# SH7_-_LOAD_MONITORING_1.net
KiCad netlist of a schematic drawn in Altium Designer
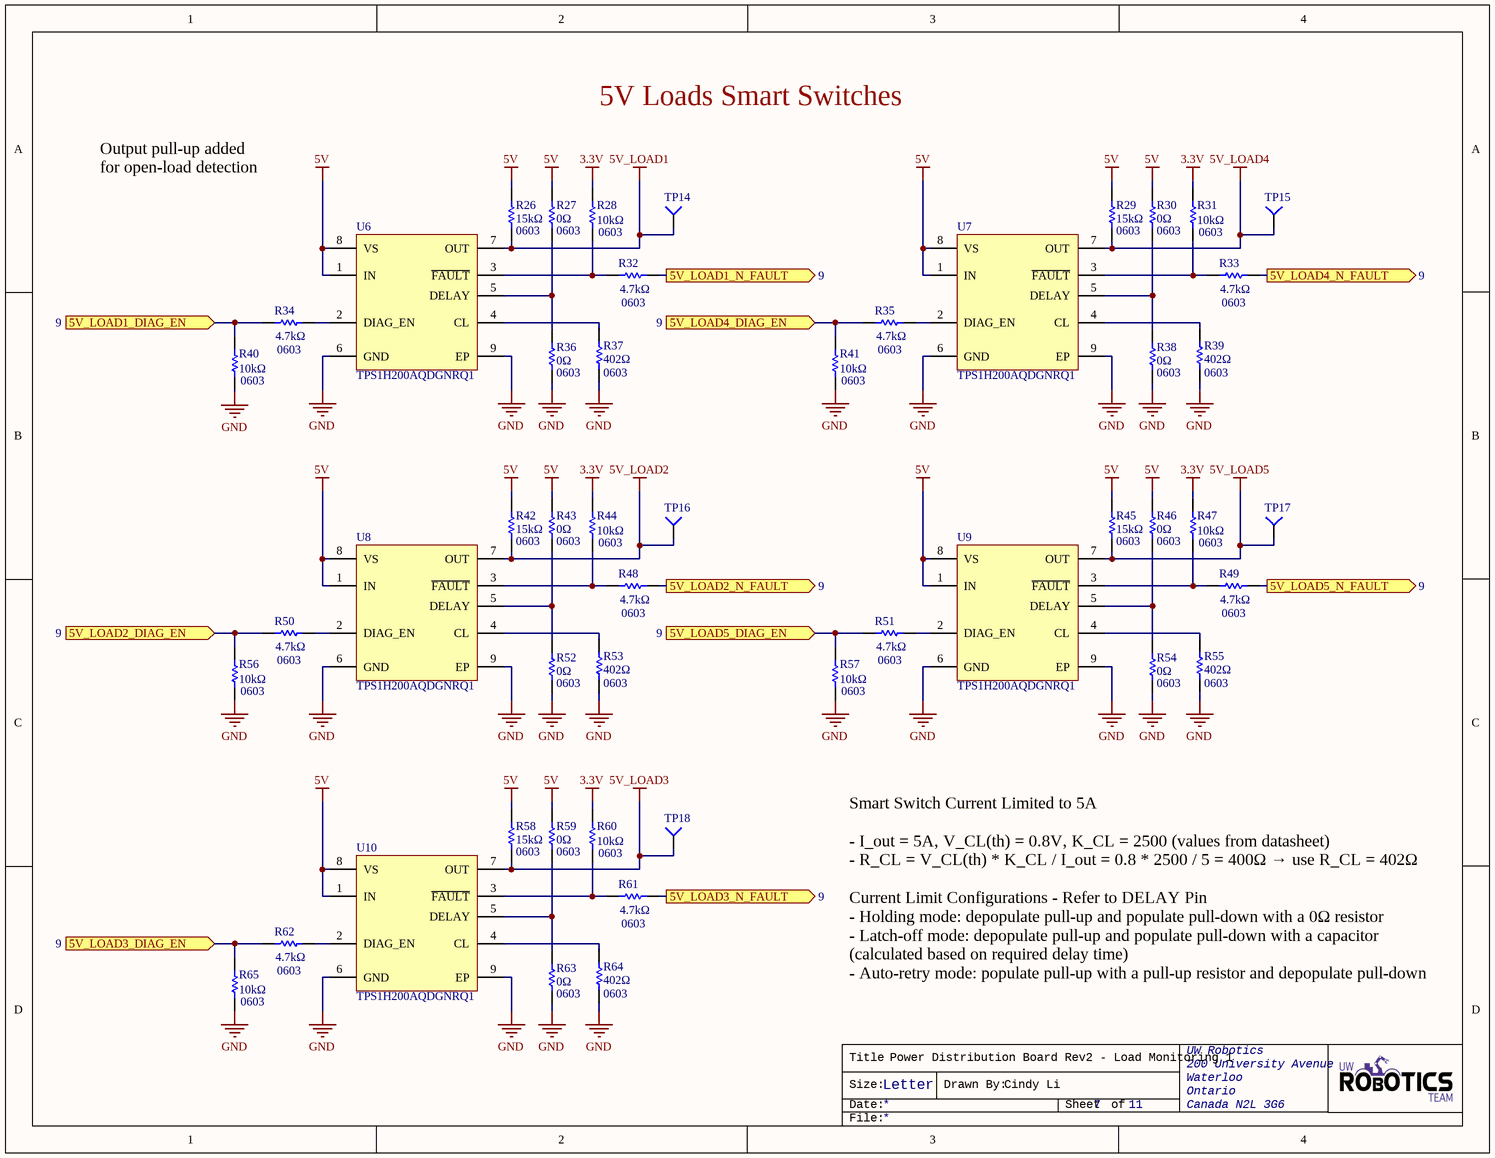
[diagram p0: SH7 - LOAD MONITORING 1.SchDoc]

(export (version "E")
  (design (tool "Eeschema 10.0.6"))
  (components
    (comp (ref "R26")
      (value "15kΩ")
      (footprint "RESC0603(1608)_N")
      (description "RES 15K OHM 5% 1/10W 0603")
      (fields
        (field (name "TOLERANCE") "5%")
        (field (name "CASE CODE (IMPERIAL)") "0603")
        (field (name "Comment") "RES_15kΩ_0603")
      )
      (libsource (lib "UWRT_Schematic_Library_2020") (part "RES_15kΩ_0603_5%"))
    )
    (comp (ref "R27")
      (value "0Ω")
      (footprint "RESC0603(1608)_N")
      (description "RES 0 OHM JUMPER 1/10W 0603")
      (fields (field (name "CASE CODE (IMPERIAL)") "0603") (field (name "Comment") "RES_0Ω_0603"))
      (libsource (lib "UWRT_Schematic_Library_2020") (part "RES_0Ω_0603"))
    )
    (comp (ref "R28")
      (value "10kΩ")
      (footprint "RESC0603(1608)_N")
      (description "RES 10K OHM 5% 1/10W 0603")
      (fields
        (field (name "TOLERANCE") "5%")
        (field (name "CASE CODE (IMPERIAL)") "0603")
        (field (name "Comment") "RES_10kΩ_0603")
      )
      (libsource (lib "UWRT_Schematic_Library_2020") (part "RES_10kΩ_0603_5%"))
    )
    (comp (ref "R29")
      (value "15kΩ")
      (footprint "RESC0603(1608)_N")
      (description "RES 15K OHM 5% 1/10W 0603")
      (fields
        (field (name "TOLERANCE") "5%")
        (field (name "CASE CODE (IMPERIAL)") "0603")
        (field (name "Comment") "RES_15kΩ_0603")
      )
      (libsource (lib "UWRT_Schematic_Library_2020") (part "RES_15kΩ_0603_5%"))
    )
    (comp (ref "R30")
      (value "0Ω")
      (footprint "RESC0603(1608)_N")
      (description "RES 0 OHM JUMPER 1/10W 0603")
      (fields (field (name "CASE CODE (IMPERIAL)") "0603") (field (name "Comment") "RES_0Ω_0603"))
      (libsource (lib "UWRT_Schematic_Library_2020") (part "RES_0Ω_0603"))
    )
    (comp (ref "R31")
      (value "10kΩ")
      (footprint "RESC0603(1608)_N")
      (description "RES 10K OHM 5% 1/10W 0603")
      (fields
        (field (name "TOLERANCE") "5%")
        (field (name "CASE CODE (IMPERIAL)") "0603")
        (field (name "Comment") "RES_10kΩ_0603")
      )
      (libsource (lib "UWRT_Schematic_Library_2020") (part "RES_10kΩ_0603_5%"))
    )
    (comp (ref "R32")
      (value "4.7kΩ")
      (footprint "RESC0603(1608)_N")
      (description "RES 4.7K OHM 5% 1/10W 0603")
      (fields
        (field (name "TOLERANCE") "5%")
        (field (name "CASE CODE (IMPERIAL)") "0603")
        (field (name "Comment") "RES_4.7kΩ_0603")
      )
      (libsource (lib "UWRT_Schematic_Library_2020") (part "RES_4.7kΩ_0603_5%"))
    )
    (comp (ref "R33")
      (value "4.7kΩ")
      (footprint "RESC0603(1608)_N")
      (description "RES 4.7K OHM 5% 1/10W 0603")
      (fields
        (field (name "TOLERANCE") "5%")
        (field (name "CASE CODE (IMPERIAL)") "0603")
        (field (name "Comment") "RES_4.7kΩ_0603")
      )
      (libsource (lib "UWRT_Schematic_Library_2020") (part "RES_4.7kΩ_0603_5%"))
    )
    (comp (ref "R34")
      (value "4.7kΩ")
      (footprint "RESC0603(1608)_N")
      (description "RES 4.7K OHM 5% 1/10W 0603")
      (fields
        (field (name "TOLERANCE") "5%")
        (field (name "CASE CODE (IMPERIAL)") "0603")
        (field (name "Comment") "RES_4.7kΩ_0603")
      )
      (libsource (lib "UWRT_Schematic_Library_2020") (part "RES_4.7kΩ_0603_5%"))
    )
    (comp (ref "R35")
      (value "4.7kΩ")
      (footprint "RESC0603(1608)_N")
      (description "RES 4.7K OHM 5% 1/10W 0603")
      (fields
        (field (name "TOLERANCE") "5%")
        (field (name "CASE CODE (IMPERIAL)") "0603")
        (field (name "Comment") "RES_4.7kΩ_0603")
      )
      (libsource (lib "UWRT_Schematic_Library_2020") (part "RES_4.7kΩ_0603_5%"))
    )
    (comp (ref "R36")
      (value "0Ω")
      (footprint "RESC0603(1608)_N")
      (description "RES 0 OHM JUMPER 1/10W 0603")
      (fields (field (name "CASE CODE (IMPERIAL)") "0603") (field (name "Comment") "RES_0Ω_0603"))
      (libsource (lib "UWRT_Schematic_Library_2020") (part "RES_0Ω_0603"))
    )
    (comp (ref "R37")
      (value "RES_402Ω_0603")
      (footprint "RESC0603(1608)_N")
      (description "RES SMD 402 OHM 0.5% 1/10W 0603")
      (fields
        (field (name "TOLERANCE") "0.5%")
        (field (name "RESISTANCE") "402Ω")
        (field (name "CASE CODE (IMPERIAL)") "0603")
      )
      (libsource (lib "UWRT_Schematic_Library_2020") (part "RES_402Ω_0603"))
    )
    (comp (ref "R38")
      (value "0Ω")
      (footprint "RESC0603(1608)_N")
      (description "RES 0 OHM JUMPER 1/10W 0603")
      (fields (field (name "CASE CODE (IMPERIAL)") "0603") (field (name "Comment") "RES_0Ω_0603"))
      (libsource (lib "UWRT_Schematic_Library_2020") (part "RES_0Ω_0603"))
    )
    (comp (ref "R39")
      (value "RES_402Ω_0603")
      (footprint "RESC0603(1608)_N")
      (description "RES SMD 402 OHM 0.5% 1/10W 0603")
      (fields
        (field (name "TOLERANCE") "0.5%")
        (field (name "RESISTANCE") "402Ω")
        (field (name "CASE CODE (IMPERIAL)") "0603")
      )
      (libsource (lib "UWRT_Schematic_Library_2020") (part "RES_402Ω_0603"))
    )
    (comp (ref "R40")
      (value "10kΩ")
      (footprint "RESC0603(1608)_N")
      (description "RES 10K OHM 5% 1/10W 0603")
      (fields
        (field (name "TOLERANCE") "5%")
        (field (name "CASE CODE (IMPERIAL)") "0603")
        (field (name "Comment") "RES_10kΩ_0603")
      )
      (libsource (lib "UWRT_Schematic_Library_2020") (part "RES_10kΩ_0603_5%"))
    )
    (comp (ref "R41")
      (value "10kΩ")
      (footprint "RESC0603(1608)_N")
      (description "RES 10K OHM 5% 1/10W 0603")
      (fields
        (field (name "TOLERANCE") "5%")
        (field (name "CASE CODE (IMPERIAL)") "0603")
        (field (name "Comment") "RES_10kΩ_0603")
      )
      (libsource (lib "UWRT_Schematic_Library_2020") (part "RES_10kΩ_0603_5%"))
    )
    (comp (ref "R42")
      (value "15kΩ")
      (footprint "RESC0603(1608)_N")
      (description "RES 15K OHM 5% 1/10W 0603")
      (fields
        (field (name "TOLERANCE") "5%")
        (field (name "CASE CODE (IMPERIAL)") "0603")
        (field (name "Comment") "RES_15kΩ_0603")
      )
      (libsource (lib "UWRT_Schematic_Library_2020") (part "RES_15kΩ_0603_5%"))
    )
    (comp (ref "R43")
      (value "0Ω")
      (footprint "RESC0603(1608)_N")
      (description "RES 0 OHM JUMPER 1/10W 0603")
      (fields (field (name "CASE CODE (IMPERIAL)") "0603") (field (name "Comment") "RES_0Ω_0603"))
      (libsource (lib "UWRT_Schematic_Library_2020") (part "RES_0Ω_0603"))
    )
    (comp (ref "R44")
      (value "10kΩ")
      (footprint "RESC0603(1608)_N")
      (description "RES 10K OHM 5% 1/10W 0603")
      (fields
        (field (name "TOLERANCE") "5%")
        (field (name "CASE CODE (IMPERIAL)") "0603")
        (field (name "Comment") "RES_10kΩ_0603")
      )
      (libsource (lib "UWRT_Schematic_Library_2020") (part "RES_10kΩ_0603_5%"))
    )
    (comp (ref "R45")
      (value "15kΩ")
      (footprint "RESC0603(1608)_N")
      (description "RES 15K OHM 5% 1/10W 0603")
      (fields
        (field (name "TOLERANCE") "5%")
        (field (name "CASE CODE (IMPERIAL)") "0603")
        (field (name "Comment") "RES_15kΩ_0603")
      )
      (libsource (lib "UWRT_Schematic_Library_2020") (part "RES_15kΩ_0603_5%"))
    )
    (comp (ref "R46")
      (value "0Ω")
      (footprint "RESC0603(1608)_N")
      (description "RES 0 OHM JUMPER 1/10W 0603")
      (fields (field (name "CASE CODE (IMPERIAL)") "0603") (field (name "Comment") "RES_0Ω_0603"))
      (libsource (lib "UWRT_Schematic_Library_2020") (part "RES_0Ω_0603"))
    )
    (comp (ref "R47")
      (value "10kΩ")
      (footprint "RESC0603(1608)_N")
      (description "RES 10K OHM 5% 1/10W 0603")
      (fields
        (field (name "TOLERANCE") "5%")
        (field (name "CASE CODE (IMPERIAL)") "0603")
        (field (name "Comment") "RES_10kΩ_0603")
      )
      (libsource (lib "UWRT_Schematic_Library_2020") (part "RES_10kΩ_0603_5%"))
    )
    (comp (ref "R48")
      (value "4.7kΩ")
      (footprint "RESC0603(1608)_N")
      (description "RES 4.7K OHM 5% 1/10W 0603")
      (fields
        (field (name "TOLERANCE") "5%")
        (field (name "CASE CODE (IMPERIAL)") "0603")
        (field (name "Comment") "RES_4.7kΩ_0603")
      )
      (libsource (lib "UWRT_Schematic_Library_2020") (part "RES_4.7kΩ_0603_5%"))
    )
    (comp (ref "R49")
      (value "4.7kΩ")
      (footprint "RESC0603(1608)_N")
      (description "RES 4.7K OHM 5% 1/10W 0603")
      (fields
        (field (name "TOLERANCE") "5%")
        (field (name "CASE CODE (IMPERIAL)") "0603")
        (field (name "Comment") "RES_4.7kΩ_0603")
      )
      (libsource (lib "UWRT_Schematic_Library_2020") (part "RES_4.7kΩ_0603_5%"))
    )
    (comp (ref "R50")
      (value "4.7kΩ")
      (footprint "RESC0603(1608)_N")
      (description "RES 4.7K OHM 5% 1/10W 0603")
      (fields
        (field (name "TOLERANCE") "5%")
        (field (name "CASE CODE (IMPERIAL)") "0603")
        (field (name "Comment") "RES_4.7kΩ_0603")
      )
      (libsource (lib "UWRT_Schematic_Library_2020") (part "RES_4.7kΩ_0603_5%"))
    )
    (comp (ref "R51")
      (value "4.7kΩ")
      (footprint "RESC0603(1608)_N")
      (description "RES 4.7K OHM 5% 1/10W 0603")
      (fields
        (field (name "TOLERANCE") "5%")
        (field (name "CASE CODE (IMPERIAL)") "0603")
        (field (name "Comment") "RES_4.7kΩ_0603")
      )
      (libsource (lib "UWRT_Schematic_Library_2020") (part "RES_4.7kΩ_0603_5%"))
    )
    (comp (ref "R52")
      (value "0Ω")
      (footprint "RESC0603(1608)_N")
      (description "RES 0 OHM JUMPER 1/10W 0603")
      (fields (field (name "CASE CODE (IMPERIAL)") "0603") (field (name "Comment") "RES_0Ω_0603"))
      (libsource (lib "UWRT_Schematic_Library_2020") (part "RES_0Ω_0603"))
    )
    (comp (ref "R53")
      (value "RES_402Ω_0603")
      (footprint "RESC0603(1608)_N")
      (description "RES SMD 402 OHM 0.5% 1/10W 0603")
      (fields
        (field (name "TOLERANCE") "0.5%")
        (field (name "RESISTANCE") "402Ω")
        (field (name "CASE CODE (IMPERIAL)") "0603")
      )
      (libsource (lib "UWRT_Schematic_Library_2020") (part "RES_402Ω_0603"))
    )
    (comp (ref "R54")
      (value "0Ω")
      (footprint "RESC0603(1608)_N")
      (description "RES 0 OHM JUMPER 1/10W 0603")
      (fields (field (name "CASE CODE (IMPERIAL)") "0603") (field (name "Comment") "RES_0Ω_0603"))
      (libsource (lib "UWRT_Schematic_Library_2020") (part "RES_0Ω_0603"))
    )
    (comp (ref "R55")
      (value "RES_402Ω_0603")
      (footprint "RESC0603(1608)_N")
      (description "RES SMD 402 OHM 0.5% 1/10W 0603")
      (fields
        (field (name "TOLERANCE") "0.5%")
        (field (name "RESISTANCE") "402Ω")
        (field (name "CASE CODE (IMPERIAL)") "0603")
      )
      (libsource (lib "UWRT_Schematic_Library_2020") (part "RES_402Ω_0603"))
    )
    (comp (ref "R56")
      (value "10kΩ")
      (footprint "RESC0603(1608)_N")
      (description "RES 10K OHM 5% 1/10W 0603")
      (fields
        (field (name "TOLERANCE") "5%")
        (field (name "CASE CODE (IMPERIAL)") "0603")
        (field (name "Comment") "RES_10kΩ_0603")
      )
      (libsource (lib "UWRT_Schematic_Library_2020") (part "RES_10kΩ_0603_5%"))
    )
    (comp (ref "R57")
      (value "10kΩ")
      (footprint "RESC0603(1608)_N")
      (description "RES 10K OHM 5% 1/10W 0603")
      (fields
        (field (name "TOLERANCE") "5%")
        (field (name "CASE CODE (IMPERIAL)") "0603")
        (field (name "Comment") "RES_10kΩ_0603")
      )
      (libsource (lib "UWRT_Schematic_Library_2020") (part "RES_10kΩ_0603_5%"))
    )
    (comp (ref "R58")
      (value "15kΩ")
      (footprint "RESC0603(1608)_N")
      (description "RES 15K OHM 5% 1/10W 0603")
      (fields
        (field (name "TOLERANCE") "5%")
        (field (name "CASE CODE (IMPERIAL)") "0603")
        (field (name "Comment") "RES_15kΩ_0603")
      )
      (libsource (lib "UWRT_Schematic_Library_2020") (part "RES_15kΩ_0603_5%"))
    )
    (comp (ref "R59")
      (value "0Ω")
      (footprint "RESC0603(1608)_N")
      (description "RES 0 OHM JUMPER 1/10W 0603")
      (fields (field (name "CASE CODE (IMPERIAL)") "0603") (field (name "Comment") "RES_0Ω_0603"))
      (libsource (lib "UWRT_Schematic_Library_2020") (part "RES_0Ω_0603"))
    )
    (comp (ref "R60")
      (value "10kΩ")
      (footprint "RESC0603(1608)_N")
      (description "RES 10K OHM 5% 1/10W 0603")
      (fields
        (field (name "TOLERANCE") "5%")
        (field (name "CASE CODE (IMPERIAL)") "0603")
        (field (name "Comment") "RES_10kΩ_0603")
      )
      (libsource (lib "UWRT_Schematic_Library_2020") (part "RES_10kΩ_0603_5%"))
    )
    (comp (ref "R61")
      (value "4.7kΩ")
      (footprint "RESC0603(1608)_N")
      (description "RES 4.7K OHM 5% 1/10W 0603")
      (fields
        (field (name "TOLERANCE") "5%")
        (field (name "CASE CODE (IMPERIAL)") "0603")
        (field (name "Comment") "RES_4.7kΩ_0603")
      )
      (libsource (lib "UWRT_Schematic_Library_2020") (part "RES_4.7kΩ_0603_5%"))
    )
    (comp (ref "R62")
      (value "4.7kΩ")
      (footprint "RESC0603(1608)_N")
      (description "RES 4.7K OHM 5% 1/10W 0603")
      (fields
        (field (name "TOLERANCE") "5%")
        (field (name "CASE CODE (IMPERIAL)") "0603")
        (field (name "Comment") "RES_4.7kΩ_0603")
      )
      (libsource (lib "UWRT_Schematic_Library_2020") (part "RES_4.7kΩ_0603_5%"))
    )
    (comp (ref "R63")
      (value "0Ω")
      (footprint "RESC0603(1608)_N")
      (description "RES 0 OHM JUMPER 1/10W 0603")
      (fields (field (name "CASE CODE (IMPERIAL)") "0603") (field (name "Comment") "RES_0Ω_0603"))
      (libsource (lib "UWRT_Schematic_Library_2020") (part "RES_0Ω_0603"))
    )
    (comp (ref "R64")
      (value "RES_402Ω_0603")
      (footprint "RESC0603(1608)_N")
      (description "RES SMD 402 OHM 0.5% 1/10W 0603")
      (fields
        (field (name "TOLERANCE") "0.5%")
        (field (name "RESISTANCE") "402Ω")
        (field (name "CASE CODE (IMPERIAL)") "0603")
      )
      (libsource (lib "UWRT_Schematic_Library_2020") (part "RES_402Ω_0603"))
    )
    (comp (ref "R65")
      (value "10kΩ")
      (footprint "RESC0603(1608)_N")
      (description "RES 10K OHM 5% 1/10W 0603")
      (fields
        (field (name "TOLERANCE") "5%")
        (field (name "CASE CODE (IMPERIAL)") "0603")
        (field (name "Comment") "RES_10kΩ_0603")
      )
      (libsource (lib "UWRT_Schematic_Library_2020") (part "RES_10kΩ_0603_5%"))
    )
    (comp (ref "TP14")
      (value "TESTPOINT_1MM_CIRCLE")
      (footprint "TESTPOINT_CIRCLE_1MM")
      (description "TESTPOINT 1MM CIRCLE")
      (libsource (lib "UWRT_Schematic_Library_2020") (part "TESTPOINT_1MM_CIRCLE"))
    )
    (comp (ref "TP15")
      (value "TESTPOINT_1MM_CIRCLE")
      (footprint "TESTPOINT_CIRCLE_1MM")
      (description "TESTPOINT 1MM CIRCLE")
      (libsource (lib "UWRT_Schematic_Library_2020") (part "TESTPOINT_1MM_CIRCLE"))
    )
    (comp (ref "TP16")
      (value "TESTPOINT_1MM_CIRCLE")
      (footprint "TESTPOINT_CIRCLE_1MM")
      (description "TESTPOINT 1MM CIRCLE")
      (libsource (lib "UWRT_Schematic_Library_2020") (part "TESTPOINT_1MM_CIRCLE"))
    )
    (comp (ref "TP17")
      (value "TESTPOINT_1MM_CIRCLE")
      (footprint "TESTPOINT_CIRCLE_1MM")
      (description "TESTPOINT 1MM CIRCLE")
      (libsource (lib "UWRT_Schematic_Library_2020") (part "TESTPOINT_1MM_CIRCLE"))
    )
    (comp (ref "TP18")
      (value "TESTPOINT_1MM_CIRCLE")
      (footprint "TESTPOINT_CIRCLE_1MM")
      (description "TESTPOINT 1MM CIRCLE")
      (libsource (lib "UWRT_Schematic_Library_2020") (part "TESTPOINT_1MM_CIRCLE"))
    )
    (comp (ref "U6")
      (value "TPS1H200A-Q1")
      (footprint "DGN0008G")
      (description "IC PWR DRIVER N-CHAN 1:1 8MSOP")
      (fields (field (name "MANUFACTURER PART NUMBER 1") "TPS1H200AQDGNRQ1"))
      (libsource (lib "UWRT_Schematic_Library_2020") (part "TPS1H200A-Q1"))
    )
    (comp (ref "U7")
      (value "TPS1H200A-Q1")
      (footprint "DGN0008G")
      (description "IC PWR DRIVER N-CHAN 1:1 8MSOP")
      (fields (field (name "MANUFACTURER PART NUMBER 1") "TPS1H200AQDGNRQ1"))
      (libsource (lib "UWRT_Schematic_Library_2020") (part "TPS1H200A-Q1"))
    )
    (comp (ref "U8")
      (value "TPS1H200A-Q1")
      (footprint "DGN0008G")
      (description "IC PWR DRIVER N-CHAN 1:1 8MSOP")
      (fields (field (name "MANUFACTURER PART NUMBER 1") "TPS1H200AQDGNRQ1"))
      (libsource (lib "UWRT_Schematic_Library_2020") (part "TPS1H200A-Q1"))
    )
    (comp (ref "U9")
      (value "TPS1H200A-Q1")
      (footprint "DGN0008G")
      (description "IC PWR DRIVER N-CHAN 1:1 8MSOP")
      (fields (field (name "MANUFACTURER PART NUMBER 1") "TPS1H200AQDGNRQ1"))
      (libsource (lib "UWRT_Schematic_Library_2020") (part "TPS1H200A-Q1"))
    )
    (comp (ref "U10")
      (value "TPS1H200A-Q1")
      (footprint "DGN0008G")
      (description "IC PWR DRIVER N-CHAN 1:1 8MSOP")
      (fields (field (name "MANUFACTURER PART NUMBER 1") "TPS1H200AQDGNRQ1"))
      (libsource (lib "UWRT_Schematic_Library_2020") (part "TPS1H200A-Q1"))
    )
  )
  (nets
    (net (code "1") (name "/5V_LOAD1_DIAG_EN") (class "Default")
      (node (ref "R34") (pin "1") (pinfunction "1_1") (pintype "passive"))
      (node (ref "R40") (pin "2") (pinfunction "2_2") (pintype "passive"))
    )
    (net (code "2") (name "/5V_LOAD1_N_FAULT") (class "Default")
      (node (ref "R32") (pin "2") (pinfunction "2_2") (pintype "passive"))
    )
    (net (code "3") (name "/5V_LOAD2_DIAG_EN") (class "Default")
      (node (ref "R50") (pin "1") (pinfunction "1_1") (pintype "passive"))
      (node (ref "R56") (pin "2") (pinfunction "2_2") (pintype "passive"))
    )
    (net (code "4") (name "/5V_LOAD2_N_FAULT") (class "Default")
      (node (ref "R48") (pin "2") (pinfunction "2_2") (pintype "passive"))
    )
    (net (code "5") (name "/5V_LOAD3_DIAG_EN") (class "Default")
      (node (ref "R62") (pin "1") (pinfunction "1_1") (pintype "passive"))
      (node (ref "R65") (pin "2") (pinfunction "2_2") (pintype "passive"))
    )
    (net (code "6") (name "/5V_LOAD3_N_FAULT") (class "Default")
      (node (ref "R61") (pin "2") (pinfunction "2_2") (pintype "passive"))
    )
    (net (code "7") (name "/5V_LOAD4_DIAG_EN") (class "Default")
      (node (ref "R35") (pin "1") (pinfunction "1_1") (pintype "passive"))
      (node (ref "R41") (pin "2") (pinfunction "2_2") (pintype "passive"))
    )
    (net (code "8") (name "/5V_LOAD4_N_FAULT") (class "Default")
      (node (ref "R33") (pin "2") (pinfunction "2_2") (pintype "passive"))
    )
    (net (code "9") (name "/5V_LOAD5_DIAG_EN") (class "Default")
      (node (ref "R51") (pin "1") (pinfunction "1_1") (pintype "passive"))
      (node (ref "R57") (pin "2") (pinfunction "2_2") (pintype "passive"))
    )
    (net (code "10") (name "/5V_LOAD5_N_FAULT") (class "Default")
      (node (ref "R49") (pin "2") (pinfunction "2_2") (pintype "passive"))
    )
    (net (code "11") (name "3.3V") (class "Default")
      (node (ref "R28") (pin "2") (pinfunction "2_2") (pintype "passive"))
      (node (ref "R31") (pin "2") (pinfunction "2_2") (pintype "passive"))
      (node (ref "R44") (pin "2") (pinfunction "2_2") (pintype "passive"))
      (node (ref "R47") (pin "2") (pinfunction "2_2") (pintype "passive"))
      (node (ref "R60") (pin "2") (pinfunction "2_2") (pintype "passive"))
    )
    (net (code "12") (name "5V") (class "Default")
      (node (ref "R26") (pin "2") (pinfunction "2_2") (pintype "passive"))
      (node (ref "R27") (pin "2") (pinfunction "2_2") (pintype "passive"))
      (node (ref "R29") (pin "2") (pinfunction "2_2") (pintype "passive"))
      (node (ref "R30") (pin "2") (pinfunction "2_2") (pintype "passive"))
      (node (ref "R42") (pin "2") (pinfunction "2_2") (pintype "passive"))
      (node (ref "R43") (pin "2") (pinfunction "2_2") (pintype "passive"))
      (node (ref "R45") (pin "2") (pinfunction "2_2") (pintype "passive"))
      (node (ref "R46") (pin "2") (pinfunction "2_2") (pintype "passive"))
      (node (ref "R58") (pin "2") (pinfunction "2_2") (pintype "passive"))
      (node (ref "R59") (pin "2") (pinfunction "2_2") (pintype "passive"))
      (node (ref "U10") (pin "1") (pinfunction "IN_1") (pintype "passive"))
      (node (ref "U10") (pin "8") (pinfunction "VS_8") (pintype "passive"))
      (node (ref "U6") (pin "1") (pinfunction "IN_1") (pintype "passive"))
      (node (ref "U6") (pin "8") (pinfunction "VS_8") (pintype "passive"))
      (node (ref "U7") (pin "1") (pinfunction "IN_1") (pintype "passive"))
      (node (ref "U7") (pin "8") (pinfunction "VS_8") (pintype "passive"))
      (node (ref "U8") (pin "1") (pinfunction "IN_1") (pintype "passive"))
      (node (ref "U8") (pin "8") (pinfunction "VS_8") (pintype "passive"))
      (node (ref "U9") (pin "1") (pinfunction "IN_1") (pintype "passive"))
      (node (ref "U9") (pin "8") (pinfunction "VS_8") (pintype "passive"))
    )
    (net (code "13") (name "5V_LOAD1") (class "Default")
      (node (ref "R26") (pin "1") (pinfunction "1_1") (pintype "passive"))
      (node (ref "TP14") (pin "1") (pinfunction "=value_1") (pintype "passive"))
      (node (ref "U6") (pin "7") (pinfunction "OUT_7") (pintype "passive"))
    )
    (net (code "14") (name "5V_LOAD2") (class "Default")
      (node (ref "R42") (pin "1") (pinfunction "1_1") (pintype "passive"))
      (node (ref "TP16") (pin "1") (pinfunction "=value_1") (pintype "passive"))
      (node (ref "U8") (pin "7") (pinfunction "OUT_7") (pintype "passive"))
    )
    (net (code "15") (name "5V_LOAD3") (class "Default")
      (node (ref "R58") (pin "1") (pinfunction "1_1") (pintype "passive"))
      (node (ref "TP18") (pin "1") (pinfunction "=value_1") (pintype "passive"))
      (node (ref "U10") (pin "7") (pinfunction "OUT_7") (pintype "passive"))
    )
    (net (code "16") (name "5V_LOAD4") (class "Default")
      (node (ref "R29") (pin "1") (pinfunction "1_1") (pintype "passive"))
      (node (ref "TP15") (pin "1") (pinfunction "=value_1") (pintype "passive"))
      (node (ref "U7") (pin "7") (pinfunction "OUT_7") (pintype "passive"))
    )
    (net (code "17") (name "5V_LOAD5") (class "Default")
      (node (ref "R45") (pin "1") (pinfunction "1_1") (pintype "passive"))
      (node (ref "TP17") (pin "1") (pinfunction "=value_1") (pintype "passive"))
      (node (ref "U9") (pin "7") (pinfunction "OUT_7") (pintype "passive"))
    )
    (net (code "18") (name "GND") (class "Default")
      (node (ref "R36") (pin "1") (pinfunction "1_1") (pintype "passive"))
      (node (ref "R37") (pin "1") (pinfunction "1_1") (pintype "passive"))
      (node (ref "R38") (pin "1") (pinfunction "1_1") (pintype "passive"))
      (node (ref "R39") (pin "1") (pinfunction "1_1") (pintype "passive"))
      (node (ref "R40") (pin "1") (pinfunction "1_1") (pintype "passive"))
      (node (ref "R41") (pin "1") (pinfunction "1_1") (pintype "passive"))
      (node (ref "R52") (pin "1") (pinfunction "1_1") (pintype "passive"))
      (node (ref "R53") (pin "1") (pinfunction "1_1") (pintype "passive"))
      (node (ref "R54") (pin "1") (pinfunction "1_1") (pintype "passive"))
      (node (ref "R55") (pin "1") (pinfunction "1_1") (pintype "passive"))
      (node (ref "R56") (pin "1") (pinfunction "1_1") (pintype "passive"))
      (node (ref "R57") (pin "1") (pinfunction "1_1") (pintype "passive"))
      (node (ref "R63") (pin "1") (pinfunction "1_1") (pintype "passive"))
      (node (ref "R64") (pin "1") (pinfunction "1_1") (pintype "passive"))
      (node (ref "R65") (pin "1") (pinfunction "1_1") (pintype "passive"))
      (node (ref "U10") (pin "6") (pinfunction "GND_6") (pintype "passive"))
      (node (ref "U10") (pin "9") (pinfunction "EP_9") (pintype "passive"))
      (node (ref "U6") (pin "6") (pinfunction "GND_6") (pintype "passive"))
      (node (ref "U6") (pin "9") (pinfunction "EP_9") (pintype "passive"))
      (node (ref "U7") (pin "6") (pinfunction "GND_6") (pintype "passive"))
      (node (ref "U7") (pin "9") (pinfunction "EP_9") (pintype "passive"))
      (node (ref "U8") (pin "6") (pinfunction "GND_6") (pintype "passive"))
      (node (ref "U8") (pin "9") (pinfunction "EP_9") (pintype "passive"))
      (node (ref "U9") (pin "6") (pinfunction "GND_6") (pintype "passive"))
      (node (ref "U9") (pin "9") (pinfunction "EP_9") (pintype "passive"))
    )
    (net (code "19") (name "Net-(U6-CL)") (class "Default")
      (node (ref "R37") (pin "2") (pinfunction "2_2") (pintype "passive"))
      (node (ref "U6") (pin "4") (pinfunction "CL_4") (pintype "passive"))
    )
    (net (code "20") (name "Net-(U6-DELAY)") (class "Default")
      (node (ref "R27") (pin "1") (pinfunction "1_1") (pintype "passive"))
      (node (ref "R36") (pin "2") (pinfunction "2_2") (pintype "passive"))
      (node (ref "U6") (pin "5") (pinfunction "DELAY_5") (pintype "passive"))
    )
    (net (code "21") (name "Net-(U6-DIAG_EN)") (class "Default")
      (node (ref "R34") (pin "2") (pinfunction "2_2") (pintype "passive"))
      (node (ref "U6") (pin "2") (pinfunction "DIAG_EN_2") (pintype "passive"))
    )
    (net (code "22") (name "Net-(U6-~{FAULT})") (class "Default")
      (node (ref "R28") (pin "1") (pinfunction "1_1") (pintype "passive"))
      (node (ref "R32") (pin "1") (pinfunction "1_1") (pintype "passive"))
      (node (ref "U6") (pin "3") (pinfunction "~{FAULT}_3") (pintype "passive"))
    )
    (net (code "23") (name "Net-(U7-CL)") (class "Default")
      (node (ref "R39") (pin "2") (pinfunction "2_2") (pintype "passive"))
      (node (ref "U7") (pin "4") (pinfunction "CL_4") (pintype "passive"))
    )
    (net (code "24") (name "Net-(U7-DELAY)") (class "Default")
      (node (ref "R30") (pin "1") (pinfunction "1_1") (pintype "passive"))
      (node (ref "R38") (pin "2") (pinfunction "2_2") (pintype "passive"))
      (node (ref "U7") (pin "5") (pinfunction "DELAY_5") (pintype "passive"))
    )
    (net (code "25") (name "Net-(U7-DIAG_EN)") (class "Default")
      (node (ref "R35") (pin "2") (pinfunction "2_2") (pintype "passive"))
      (node (ref "U7") (pin "2") (pinfunction "DIAG_EN_2") (pintype "passive"))
    )
    (net (code "26") (name "Net-(U7-~{FAULT})") (class "Default")
      (node (ref "R31") (pin "1") (pinfunction "1_1") (pintype "passive"))
      (node (ref "R33") (pin "1") (pinfunction "1_1") (pintype "passive"))
      (node (ref "U7") (pin "3") (pinfunction "~{FAULT}_3") (pintype "passive"))
    )
    (net (code "27") (name "Net-(U8-CL)") (class "Default")
      (node (ref "R53") (pin "2") (pinfunction "2_2") (pintype "passive"))
      (node (ref "U8") (pin "4") (pinfunction "CL_4") (pintype "passive"))
    )
    (net (code "28") (name "Net-(U8-DELAY)") (class "Default")
      (node (ref "R43") (pin "1") (pinfunction "1_1") (pintype "passive"))
      (node (ref "R52") (pin "2") (pinfunction "2_2") (pintype "passive"))
      (node (ref "U8") (pin "5") (pinfunction "DELAY_5") (pintype "passive"))
    )
    (net (code "29") (name "Net-(U8-DIAG_EN)") (class "Default")
      (node (ref "R50") (pin "2") (pinfunction "2_2") (pintype "passive"))
      (node (ref "U8") (pin "2") (pinfunction "DIAG_EN_2") (pintype "passive"))
    )
    (net (code "30") (name "Net-(U8-~{FAULT})") (class "Default")
      (node (ref "R44") (pin "1") (pinfunction "1_1") (pintype "passive"))
      (node (ref "R48") (pin "1") (pinfunction "1_1") (pintype "passive"))
      (node (ref "U8") (pin "3") (pinfunction "~{FAULT}_3") (pintype "passive"))
    )
    (net (code "31") (name "Net-(U9-CL)") (class "Default")
      (node (ref "R55") (pin "2") (pinfunction "2_2") (pintype "passive"))
      (node (ref "U9") (pin "4") (pinfunction "CL_4") (pintype "passive"))
    )
    (net (code "32") (name "Net-(U9-DELAY)") (class "Default")
      (node (ref "R46") (pin "1") (pinfunction "1_1") (pintype "passive"))
      (node (ref "R54") (pin "2") (pinfunction "2_2") (pintype "passive"))
      (node (ref "U9") (pin "5") (pinfunction "DELAY_5") (pintype "passive"))
    )
    (net (code "33") (name "Net-(U9-DIAG_EN)") (class "Default")
      (node (ref "R51") (pin "2") (pinfunction "2_2") (pintype "passive"))
      (node (ref "U9") (pin "2") (pinfunction "DIAG_EN_2") (pintype "passive"))
    )
    (net (code "34") (name "Net-(U9-~{FAULT})") (class "Default")
      (node (ref "R47") (pin "1") (pinfunction "1_1") (pintype "passive"))
      (node (ref "R49") (pin "1") (pinfunction "1_1") (pintype "passive"))
      (node (ref "U9") (pin "3") (pinfunction "~{FAULT}_3") (pintype "passive"))
    )
    (net (code "35") (name "Net-(U10-CL)") (class "Default")
      (node (ref "R64") (pin "2") (pinfunction "2_2") (pintype "passive"))
      (node (ref "U10") (pin "4") (pinfunction "CL_4") (pintype "passive"))
    )
    (net (code "36") (name "Net-(U10-DELAY)") (class "Default")
      (node (ref "R59") (pin "1") (pinfunction "1_1") (pintype "passive"))
      (node (ref "R63") (pin "2") (pinfunction "2_2") (pintype "passive"))
      (node (ref "U10") (pin "5") (pinfunction "DELAY_5") (pintype "passive"))
    )
    (net (code "37") (name "Net-(U10-DIAG_EN)") (class "Default")
      (node (ref "R62") (pin "2") (pinfunction "2_2") (pintype "passive"))
      (node (ref "U10") (pin "2") (pinfunction "DIAG_EN_2") (pintype "passive"))
    )
    (net (code "38") (name "Net-(U10-~{FAULT})") (class "Default")
      (node (ref "R60") (pin "1") (pinfunction "1_1") (pintype "passive"))
      (node (ref "R61") (pin "1") (pinfunction "1_1") (pintype "passive"))
      (node (ref "U10") (pin "3") (pinfunction "~{FAULT}_3") (pintype "passive"))
    )
  )
)
